# seguidor_LDR_22.net
KiCad netlist of a schematic drawn in EAGLE
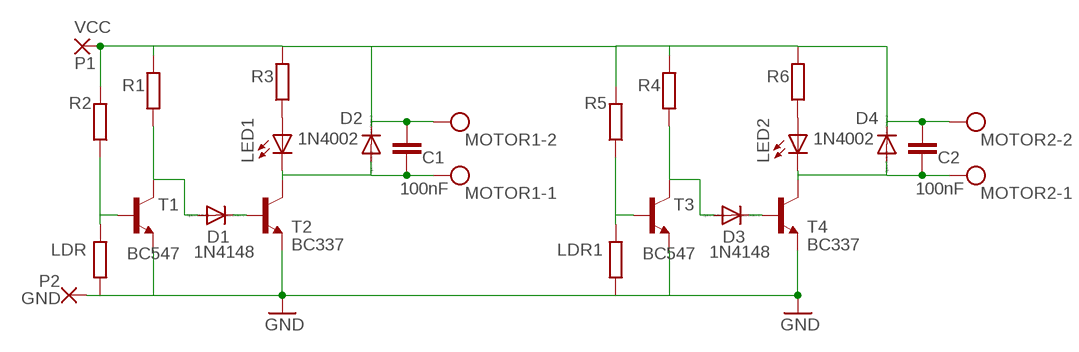
[diagram p0: schematic, sheet 1]

(export (version "E")
  (design (tool "Eeschema 10.0.6"))
  (components
    (comp (ref "C1")
      (value "100nF")
      (footprint "eagle-import:C050-025X075")
      (libsource (lib "eagle-import") (part "C-EU050-025X075"))
    )
    (comp (ref "C2")
      (value "100nF")
      (footprint "eagle-import:C050-025X075")
      (libsource (lib "eagle-import") (part "C-EU050-025X075"))
    )
    (comp (ref "D1")
      (value "1N4148")
      (footprint "eagle-import:DO35-10")
      (libsource (lib "eagle-import") (part "1N4148DO35-10"))
    )
    (comp (ref "D2")
      (value "1N4002")
      (footprint "eagle-import:DO41-10")
      (libsource (lib "eagle-import") (part "1N4004"))
    )
    (comp (ref "D3")
      (value "1N4148")
      (footprint "eagle-import:DO35-10")
      (libsource (lib "eagle-import") (part "1N4148DO35-10"))
    )
    (comp (ref "D4")
      (value "1N4002")
      (footprint "eagle-import:DO41-10")
      (libsource (lib "eagle-import") (part "1N4004"))
    )
    (comp (ref "GND")
      (value "P2")
      (footprint "eagle-import:2,15_1,0")
      (libsource (lib "eagle-import") (part "WIREPAD2,15/1,0"))
    )
    (comp (ref "LDR")
      (value "R-EU_0204/5")
      (footprint "eagle-import:0204_5")
      (libsource (lib "eagle-import") (part "R-EU_0204/5"))
    )
    (comp (ref "LDR1")
      (value "R-EU_0204/5")
      (footprint "eagle-import:0204_5")
      (libsource (lib "eagle-import") (part "R-EU_0204/5"))
    )
    (comp (ref "LED1")
      (value "LED3MM")
      (footprint "eagle-import:LED3MM")
      (libsource (lib "eagle-import") (part "LED3MM"))
    )
    (comp (ref "LED2")
      (value "LED3MM")
      (footprint "eagle-import:LED3MM")
      (libsource (lib "eagle-import") (part "LED3MM"))
    )
    (comp (ref "MOTOR1")
      (value "AK500/2")
      (footprint "eagle-import:AK500_2")
      (libsource (lib "eagle-import") (part "AK500/2"))
    )
    (comp (ref "MOTOR2")
      (value "AK500/2")
      (footprint "eagle-import:AK500_2")
      (libsource (lib "eagle-import") (part "AK500/2"))
    )
    (comp (ref "R1")
      (value "R-EU_0207/10")
      (footprint "eagle-import:0207_10")
      (libsource (lib "eagle-import") (part "R-EU_0207/10"))
    )
    (comp (ref "R2")
      (value "R-EU_0207/10")
      (footprint "eagle-import:0207_10")
      (libsource (lib "eagle-import") (part "R-EU_0207/10"))
    )
    (comp (ref "R3")
      (value "R-EU_0207/10")
      (footprint "eagle-import:0207_10")
      (libsource (lib "eagle-import") (part "R-EU_0207/10"))
    )
    (comp (ref "R4")
      (value "R-EU_0207/10")
      (footprint "eagle-import:0207_10")
      (libsource (lib "eagle-import") (part "R-EU_0207/10"))
    )
    (comp (ref "R5")
      (value "R-EU_0207/10")
      (footprint "eagle-import:0207_10")
      (libsource (lib "eagle-import") (part "R-EU_0207/10"))
    )
    (comp (ref "R6")
      (value "R-EU_0207/10")
      (footprint "eagle-import:0207_10")
      (libsource (lib "eagle-import") (part "R-EU_0207/10"))
    )
    (comp (ref "T1")
      (value "BC547")
      (footprint "eagle-import:TO92-CBE")
      (libsource (lib "eagle-import") (part "-NPN-TO92-CBEBC337-16"))
    )
    (comp (ref "T2")
      (value "BC337")
      (footprint "eagle-import:TO92-CBE")
      (libsource (lib "eagle-import") (part "-NPN-TO92-CBEBC337-16"))
    )
    (comp (ref "T3")
      (value "BC547")
      (footprint "eagle-import:TO92-CBE")
      (libsource (lib "eagle-import") (part "-NPN-TO92-CBEBC337-16"))
    )
    (comp (ref "T4")
      (value "BC337")
      (footprint "eagle-import:TO92-CBE")
      (libsource (lib "eagle-import") (part "-NPN-TO92-CBEBC337-16"))
    )
    (comp (ref "VCC")
      (value "P1")
      (footprint "eagle-import:2,15_1,0")
      (libsource (lib "eagle-import") (part "WIREPAD2,15/1,0"))
    )
  )
  (nets
    (net (code "1") (name "GND") (class "Default")
      (node (ref "GND") (pin "1") (pinfunction "P_1") (pintype "passive"))
      (node (ref "LDR") (pin "1") (pinfunction "1_1") (pintype "passive"))
      (node (ref "LDR1") (pin "1") (pinfunction "1_1") (pintype "passive"))
      (node (ref "T1") (pin "E") (pinfunction "E_E") (pintype "passive"))
      (node (ref "T2") (pin "E") (pinfunction "E_E") (pintype "passive"))
      (node (ref "T3") (pin "E") (pinfunction "E_E") (pintype "passive"))
      (node (ref "T4") (pin "E") (pinfunction "E_E") (pintype "passive"))
    )
    (net (code "2") (name "Net-(D1-PadA)") (class "Default")
      (node (ref "D1") (pin "A") (pinfunction "A_A") (pintype "passive"))
      (node (ref "R1") (pin "1") (pinfunction "1_1") (pintype "passive"))
      (node (ref "T1") (pin "C") (pinfunction "C_C") (pintype "passive"))
    )
    (net (code "3") (name "Net-(D1-PadC)") (class "Default")
      (node (ref "D1") (pin "C") (pinfunction "C_C") (pintype "passive"))
      (node (ref "T2") (pin "B") (pinfunction "B_B") (pintype "passive"))
    )
    (net (code "4") (name "Net-(D3-PadA)") (class "Default")
      (node (ref "D3") (pin "A") (pinfunction "A_A") (pintype "passive"))
      (node (ref "R4") (pin "1") (pinfunction "1_1") (pintype "passive"))
      (node (ref "T3") (pin "C") (pinfunction "C_C") (pintype "passive"))
    )
    (net (code "5") (name "Net-(D3-PadC)") (class "Default")
      (node (ref "D3") (pin "C") (pinfunction "C_C") (pintype "passive"))
      (node (ref "T4") (pin "B") (pinfunction "B_B") (pintype "passive"))
    )
    (net (code "6") (name "Net-(LDR-Pad2)") (class "Default")
      (node (ref "LDR") (pin "2") (pinfunction "2_2") (pintype "passive"))
      (node (ref "R2") (pin "1") (pinfunction "1_1") (pintype "passive"))
      (node (ref "T1") (pin "B") (pinfunction "B_B") (pintype "passive"))
    )
    (net (code "7") (name "Net-(LDR1-Pad2)") (class "Default")
      (node (ref "LDR1") (pin "2") (pinfunction "2_2") (pintype "passive"))
      (node (ref "R5") (pin "1") (pinfunction "1_1") (pintype "passive"))
      (node (ref "T3") (pin "B") (pinfunction "B_B") (pintype "passive"))
    )
    (net (code "8") (name "Net-(LED1-C)") (class "Default")
      (node (ref "C1") (pin "2") (pinfunction "2_2") (pintype "passive"))
      (node (ref "D2") (pin "A") (pinfunction "A_A") (pintype "passive"))
      (node (ref "LED1") (pin "K") (pinfunction "C_K") (pintype "passive"))
      (node (ref "MOTOR1") (pin "1") (pinfunction "KL_1") (pintype "passive"))
      (node (ref "T2") (pin "C") (pinfunction "C_C") (pintype "passive"))
    )
    (net (code "9") (name "Net-(LED1-PadA)") (class "Default")
      (node (ref "LED1") (pin "A") (pinfunction "A_A") (pintype "passive"))
      (node (ref "R3") (pin "1") (pinfunction "1_1") (pintype "passive"))
    )
    (net (code "10") (name "Net-(LED2-C)") (class "Default")
      (node (ref "C2") (pin "2") (pinfunction "2_2") (pintype "passive"))
      (node (ref "D4") (pin "A") (pinfunction "A_A") (pintype "passive"))
      (node (ref "LED2") (pin "K") (pinfunction "C_K") (pintype "passive"))
      (node (ref "MOTOR2") (pin "1") (pinfunction "KL_1") (pintype "passive"))
      (node (ref "T4") (pin "C") (pinfunction "C_C") (pintype "passive"))
    )
    (net (code "11") (name "Net-(LED2-PadA)") (class "Default")
      (node (ref "LED2") (pin "A") (pinfunction "A_A") (pintype "passive"))
      (node (ref "R6") (pin "1") (pinfunction "1_1") (pintype "passive"))
    )
    (net (code "12") (name "Net-(MOTOR1B-KL)") (class "Default")
      (node (ref "C1") (pin "1") (pinfunction "1_1") (pintype "passive"))
      (node (ref "C2") (pin "1") (pinfunction "1_1") (pintype "passive"))
      (node (ref "D2") (pin "C") (pinfunction "C_C") (pintype "passive"))
      (node (ref "D4") (pin "C") (pinfunction "C_C") (pintype "passive"))
      (node (ref "MOTOR1") (pin "2") (pinfunction "KL_2") (pintype "passive"))
      (node (ref "MOTOR2") (pin "2") (pinfunction "KL_2") (pintype "passive"))
      (node (ref "R1") (pin "2") (pinfunction "2_2") (pintype "passive"))
      (node (ref "R2") (pin "2") (pinfunction "2_2") (pintype "passive"))
      (node (ref "R3") (pin "2") (pinfunction "2_2") (pintype "passive"))
      (node (ref "R4") (pin "2") (pinfunction "2_2") (pintype "passive"))
      (node (ref "R5") (pin "2") (pinfunction "2_2") (pintype "passive"))
      (node (ref "R6") (pin "2") (pinfunction "2_2") (pintype "passive"))
      (node (ref "VCC") (pin "1") (pinfunction "P_1") (pintype "passive"))
    )
  )
)
